# eagle-revg.net
KiCad netlist of a schematic drawn in EAGLE
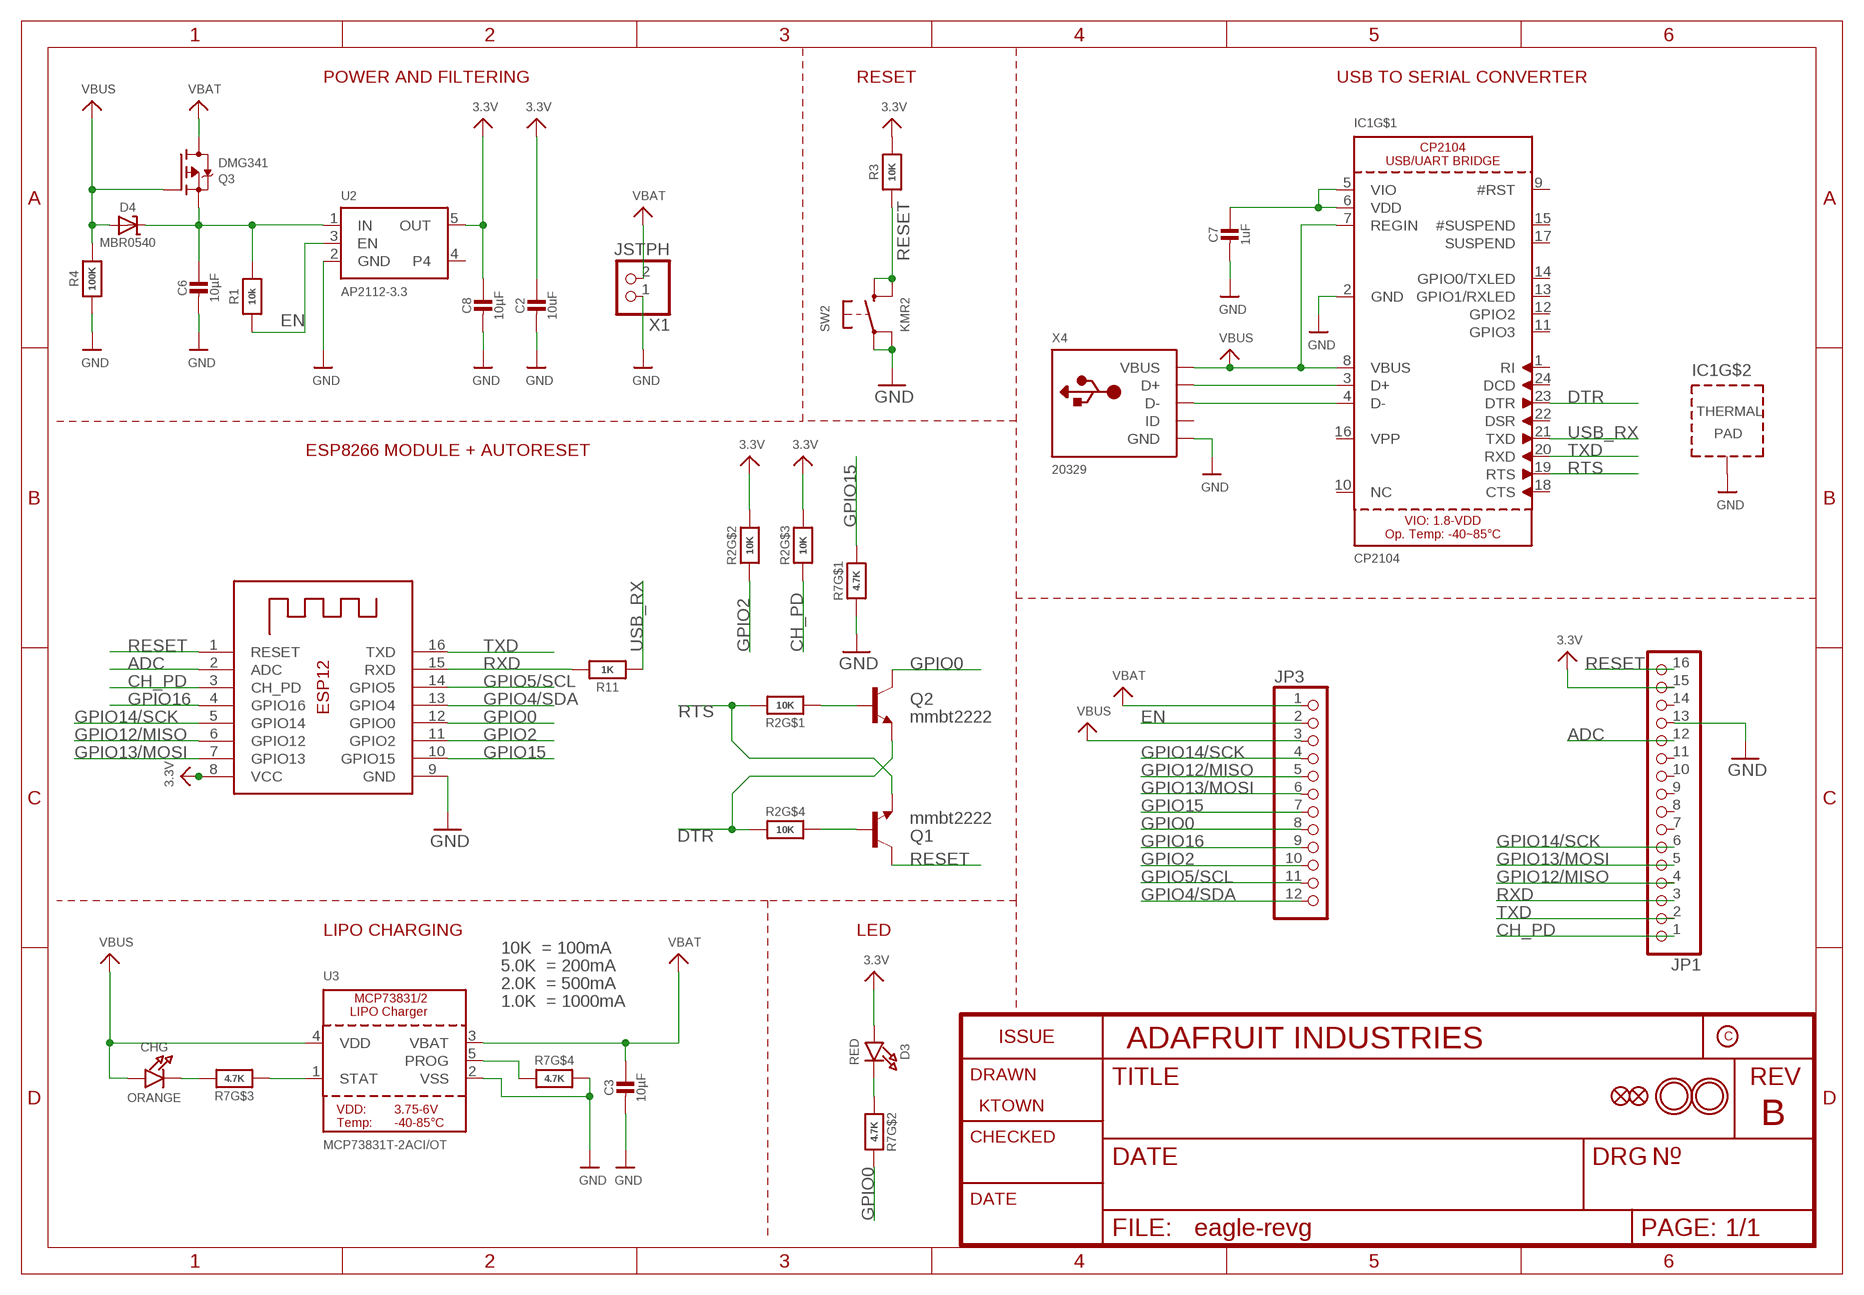
[diagram p0: schematic, sheet 1]

(export (version "E")
  (design (tool "Eeschema 10.0.6"))
  (components
    (comp (ref "C2")
      (value "10uF")
      (footprint "eagle-import:0805_10MGAP")
      (libsource (lib "eagle-import") (part "CAP_CERAMIC0805_10MGAP"))
    )
    (comp (ref "C3")
      (value "10µF")
      (footprint "eagle-import:0805-NO")
      (libsource (lib "eagle-import") (part "CAP_CERAMIC0805-NOOUTLINE"))
    )
    (comp (ref "C6")
      (value "10µF")
      (footprint "eagle-import:0805-NO")
      (libsource (lib "eagle-import") (part "CAP_CERAMIC0805-NOOUTLINE"))
    )
    (comp (ref "C7")
      (value "1uF")
      (footprint "eagle-import:0603-NO")
      (libsource (lib "eagle-import") (part "CAP_CERAMIC0603_NO"))
    )
    (comp (ref "C8")
      (value "10µF")
      (footprint "eagle-import:0805-NO")
      (fields (field (name "REV") "G"))
      (libsource (lib "eagle-import") (part "CAP_CERAMIC0805-NOOUTLINE"))
    )
    (comp (ref "CHG")
      (value "ORANGE")
      (footprint "eagle-import:CHIPLED_0603_NOOUTLINE")
      (libsource (lib "eagle-import") (part "LED0603_NOOUTLINE"))
    )
    (comp (ref "D3")
      (value "RED")
      (footprint "eagle-import:CHIPLED_0603_NOOUTLINE")
      (libsource (lib "eagle-import") (part "LED0603_NOOUTLINE"))
    )
    (comp (ref "D4")
      (value "MBR0540")
      (footprint "eagle-import:SOD-123")
      (libsource (lib "eagle-import") (part "DIODE-SCHOTTKYSOD-123"))
    )
    (comp (ref "IC1")
      (value "CP2104")
      (footprint "eagle-import:QFN24_4MM_SMSC")
      (libsource (lib "eagle-import") (part "CP2104"))
    )
    (comp (ref "JP1")
      (value "HEADER-1X16ROUND")
      (footprint "eagle-import:1X16_ROUND")
      (libsource (lib "eagle-import") (part "HEADER-1X16ROUND"))
    )
    (comp (ref "JP3")
      (value "HEADER-1X12")
      (footprint "eagle-import:1X12_ROUND")
      (libsource (lib "eagle-import") (part "HEADER-1X12"))
    )
    (comp (ref "Q1")
      (value "mmbt2222")
      (footprint "eagle-import:SOT23-3")
      (libsource (lib "eagle-import") (part "TRANSISTOR_NPNSOT23-3"))
    )
    (comp (ref "Q2")
      (value "mmbt2222")
      (footprint "eagle-import:SOT23-3")
      (libsource (lib "eagle-import") (part "TRANSISTOR_NPNSOT23-3"))
    )
    (comp (ref "Q3")
      (value "DMG341")
      (footprint "eagle-import:SOT23-R")
      (libsource (lib "eagle-import") (part "MOSFET-P"))
    )
    (comp (ref "R1")
      (value "10k")
      (footprint "eagle-import:0603-NO")
      (libsource (lib "eagle-import") (part "RESISTOR_0603_NOOUT"))
    )
    (comp (ref "R2")
      (value "10K")
      (footprint "eagle-import:RESPACK_4X0603_NO")
      (libsource (lib "eagle-import") (part "RESISTOR_4PACK_NO"))
    )
    (comp (ref "R3")
      (value "10K")
      (footprint "eagle-import:0603-NO")
      (libsource (lib "eagle-import") (part "RESISTOR_0603_NOOUT"))
    )
    (comp (ref "R4")
      (value "100K")
      (footprint "eagle-import:0603-NO")
      (libsource (lib "eagle-import") (part "RESISTOR_0603_NOOUT"))
    )
    (comp (ref "R7")
      (value "4.7K")
      (footprint "eagle-import:RESPACK_4X0603_NO")
      (libsource (lib "eagle-import") (part "RESISTOR_4PACK_NO"))
    )
    (comp (ref "R11")
      (value "1K")
      (footprint "eagle-import:0603-NO")
      (libsource (lib "eagle-import") (part "RESISTOR_0603_NOOUT"))
    )
    (comp (ref "SW2")
      (value "KMR2")
      (footprint "eagle-import:BTN_KMR2_4.6X2.8")
      (libsource (lib "eagle-import") (part "SWITCH_TACT_SMT4.6X2.8"))
    )
    (comp (ref "U$31")
      (value "MOUNTINGHOLE2.5")
      (footprint "eagle-import:MOUNTINGHOLE_2.5_PLATED")
      (libsource (lib "eagle-import") (part "MOUNTINGHOLE2.5"))
    )
    (comp (ref "U$32")
      (value "MOUNTINGHOLE2.5")
      (footprint "eagle-import:MOUNTINGHOLE_2.5_PLATED")
      (libsource (lib "eagle-import") (part "MOUNTINGHOLE2.5"))
    )
    (comp (ref "U$34")
      (value "FIDUCIAL_1MM")
      (footprint "eagle-import:FIDUCIAL_1MM")
      (libsource (lib "eagle-import") (part "FIDUCIAL_1MM"))
    )
    (comp (ref "U$35")
      (value "FIDUCIAL_1MM")
      (footprint "eagle-import:FIDUCIAL_1MM")
      (libsource (lib "eagle-import") (part "FIDUCIAL_1MM"))
    )
    (comp (ref "U2")
      (value "AP2112-3.3")
      (footprint "eagle-import:SOT23-5")
      (libsource (lib "eagle-import") (part "VREG_SOT23-5"))
    )
    (comp (ref "U3")
      (value "MCP73831T-2ACI/OT")
      (footprint "eagle-import:SOT23-5")
      (libsource (lib "eagle-import") (part "MCP73831/2"))
    )
    (comp (ref "X1")
      (value "JSTPH")
      (footprint "eagle-import:JSTPH2_BATT")
      (libsource (lib "eagle-import") (part "CON_JST_PH_2PIN_BATT"))
    )
    (comp (ref "X3")
      (value "ESP-12F")
      (footprint "eagle-import:ESP-12F")
      (libsource (lib "eagle-import") (part "ESP-12_DOIT_ESP8266"))
    )
    (comp (ref "X4")
      (value "20329")
      (footprint "eagle-import:4UCONN_20329_V2")
      (libsource (lib "eagle-import") (part "USB_MICRO_20329_V2"))
    )
  )
  (nets
    (net (code "1") (name "/ADC") (class "Default")
      (node (ref "JP1") (pin "12") (pinfunction "12_12") (pintype "passive"))
      (node (ref "X3") (pin "2") (pinfunction "ADC_2") (pintype "passive"))
    )
    (net (code "2") (name "/CH_PD") (class "Default")
      (node (ref "JP1") (pin "1") (pinfunction "1_1") (pintype "passive"))
      (node (ref "R2") (pin "3") (pinfunction "1_3") (pintype "passive"))
      (node (ref "X3") (pin "3") (pinfunction "CH_PD_3") (pintype "input"))
    )
    (net (code "3") (name "/DTR") (class "Default")
      (node (ref "IC1") (pin "23") (pinfunction "DTR_23") (pintype "output"))
      (node (ref "Q2") (pin "2") (pinfunction "E_2") (pintype "passive"))
      (node (ref "R2") (pin "4") (pinfunction "1_4") (pintype "passive"))
    )
    (net (code "4") (name "/EN") (class "Default")
      (node (ref "JP3") (pin "2") (pinfunction "2_2") (pintype "passive"))
      (node (ref "R1") (pin "1") (pinfunction "1_1") (pintype "passive"))
      (node (ref "U2") (pin "3") (pinfunction "EN_3") (pintype "input"))
    )
    (net (code "5") (name "/GPIO0") (class "Default")
      (node (ref "JP3") (pin "8") (pinfunction "8_8") (pintype "passive"))
      (node (ref "Q2") (pin "3") (pinfunction "C_3") (pintype "passive"))
      (node (ref "R7") (pin "7") (pinfunction "2_7") (pintype "passive"))
      (node (ref "X3") (pin "12") (pinfunction "GPIO0_12") (pintype "bidirectional"))
    )
    (net (code "6") (name "/GPIO2") (class "Default")
      (node (ref "JP3") (pin "10") (pinfunction "10_10") (pintype "passive"))
      (node (ref "R2") (pin "2") (pinfunction "1_2") (pintype "passive"))
      (node (ref "X3") (pin "11") (pinfunction "GPIO2_11") (pintype "bidirectional"))
    )
    (net (code "7") (name "/GPIO4{slash}SDA") (class "Default")
      (node (ref "JP3") (pin "12") (pinfunction "12_12") (pintype "passive"))
      (node (ref "X3") (pin "13") (pinfunction "GPIO4_13") (pintype "bidirectional"))
    )
    (net (code "8") (name "/GPIO5{slash}SCL") (class "Default")
      (node (ref "JP3") (pin "11") (pinfunction "11_11") (pintype "passive"))
      (node (ref "X3") (pin "14") (pinfunction "GPIO5_14") (pintype "bidirectional"))
    )
    (net (code "9") (name "/GPIO12{slash}MISO") (class "Default")
      (node (ref "JP1") (pin "4") (pinfunction "4_4") (pintype "passive"))
      (node (ref "JP3") (pin "5") (pinfunction "5_5") (pintype "passive"))
      (node (ref "X3") (pin "6") (pinfunction "GPIO12_6") (pintype "bidirectional"))
    )
    (net (code "10") (name "/GPIO13{slash}MOSI") (class "Default")
      (node (ref "JP1") (pin "5") (pinfunction "5_5") (pintype "passive"))
      (node (ref "JP3") (pin "6") (pinfunction "6_6") (pintype "passive"))
      (node (ref "X3") (pin "7") (pinfunction "GPIO13_7") (pintype "bidirectional"))
    )
    (net (code "11") (name "/GPIO14{slash}SCK") (class "Default")
      (node (ref "JP1") (pin "6") (pinfunction "6_6") (pintype "passive"))
      (node (ref "JP3") (pin "4") (pinfunction "4_4") (pintype "passive"))
      (node (ref "X3") (pin "5") (pinfunction "GPIO14_5") (pintype "bidirectional"))
    )
    (net (code "12") (name "/GPIO15") (class "Default")
      (node (ref "JP3") (pin "7") (pinfunction "7_7") (pintype "passive"))
      (node (ref "R7") (pin "8") (pinfunction "2_8") (pintype "passive"))
      (node (ref "X3") (pin "10") (pinfunction "GPIO15_10") (pintype "bidirectional"))
    )
    (net (code "13") (name "/GPIO16") (class "Default")
      (node (ref "JP3") (pin "9") (pinfunction "9_9") (pintype "passive"))
      (node (ref "X3") (pin "4") (pinfunction "GPIO16_4") (pintype "bidirectional"))
    )
    (net (code "14") (name "/RESET") (class "Default")
      (node (ref "JP1") (pin "16") (pinfunction "16_16") (pintype "passive"))
      (node (ref "Q1") (pin "3") (pinfunction "C_3") (pintype "passive"))
      (node (ref "R3") (pin "1") (pinfunction "1_1") (pintype "passive"))
      (node (ref "SW2") (pin "B") (pinfunction "S_B") (pintype "passive"))
      (node (ref "SW2") (pin "B'") (pinfunction "S1_B'") (pintype "passive"))
      (node (ref "X3") (pin "1") (pinfunction "RESET_1") (pintype "input"))
    )
    (net (code "15") (name "/RTS") (class "Default")
      (node (ref "IC1") (pin "19") (pinfunction "RTS_19") (pintype "output"))
      (node (ref "Q1") (pin "2") (pinfunction "E_2") (pintype "passive"))
      (node (ref "R2") (pin "8") (pinfunction "2_8") (pintype "passive"))
    )
    (net (code "16") (name "/RXD") (class "Default")
      (node (ref "JP1") (pin "3") (pinfunction "3_3") (pintype "passive"))
      (node (ref "R11") (pin "2") (pinfunction "2_2") (pintype "passive"))
      (node (ref "X3") (pin "15") (pinfunction "RXD_15") (pintype "input"))
    )
    (net (code "17") (name "/TXD") (class "Default")
      (node (ref "IC1") (pin "20") (pinfunction "RXD_20") (pintype "input"))
      (node (ref "JP1") (pin "2") (pinfunction "2_2") (pintype "passive"))
      (node (ref "X3") (pin "16") (pinfunction "TXD_16") (pintype "output"))
    )
    (net (code "18") (name "/USB_RX") (class "Default")
      (node (ref "IC1") (pin "21") (pinfunction "TXD_21") (pintype "output"))
      (node (ref "R11") (pin "1") (pinfunction "1_1") (pintype "passive"))
    )
    (net (code "19") (name "3.3V") (class "Default")
      (node (ref "C2") (pin "1") (pinfunction "1_1") (pintype "passive"))
      (node (ref "C8") (pin "1") (pinfunction "1_1") (pintype "passive"))
      (node (ref "D3") (pin "A") (pinfunction "A_A") (pintype "passive"))
      (node (ref "JP1") (pin "15") (pinfunction "15_15") (pintype "passive"))
      (node (ref "R2") (pin "6") (pinfunction "2_6") (pintype "passive"))
      (node (ref "R2") (pin "7") (pinfunction "2_7") (pintype "passive"))
      (node (ref "R3") (pin "2") (pinfunction "2_2") (pintype "passive"))
      (node (ref "U2") (pin "5") (pinfunction "OUT_5") (pintype "power_in"))
      (node (ref "X3") (pin "8") (pinfunction "VCC_8") (pintype "power_in"))
    )
    (net (code "20") (name "GND") (class "Default")
      (node (ref "C2") (pin "2") (pinfunction "2_2") (pintype "passive"))
      (node (ref "C3") (pin "2") (pinfunction "2_2") (pintype "passive"))
      (node (ref "C6") (pin "2") (pinfunction "2_2") (pintype "passive"))
      (node (ref "C7") (pin "2") (pinfunction "2_2") (pintype "passive"))
      (node (ref "C8") (pin "2") (pinfunction "2_2") (pintype "passive"))
      (node (ref "IC1") (pin "2") (pinfunction "GND_2") (pintype "power_in"))
      (node (ref "IC1") (pin "THERM") (pinfunction "TP_THERM") (pintype "power_in"))
      (node (ref "JP1") (pin "13") (pinfunction "13_13") (pintype "passive"))
      (node (ref "R4") (pin "1") (pinfunction "1_1") (pintype "passive"))
      (node (ref "R7") (pin "1") (pinfunction "1_1") (pintype "passive"))
      (node (ref "R7") (pin "5") (pinfunction "2_5") (pintype "passive"))
      (node (ref "SW2") (pin "A") (pinfunction "P_A") (pintype "passive"))
      (node (ref "SW2") (pin "A'") (pinfunction "P1_A'") (pintype "passive"))
      (node (ref "U2") (pin "2") (pinfunction "GND_2") (pintype "power_in"))
      (node (ref "U3") (pin "2") (pinfunction "VSS_2") (pintype "power_in"))
      (node (ref "X1") (pin "1") (pinfunction "1_1") (pintype "passive"))
      (node (ref "X3") (pin "9") (pinfunction "GND_9") (pintype "power_in"))
      (node (ref "X4") (pin "BASE@1") (pinfunction "GND_BASE@1") (pintype "power_in"))
      (node (ref "X4") (pin "BASE@2") (pinfunction "GND_BASE@2") (pintype "power_in"))
      (node (ref "X4") (pin "GND") (pinfunction "GND_GND") (pintype "power_in"))
      (node (ref "X4") (pin "SPRT@1") (pinfunction "GND_SPRT@1") (pintype "power_in"))
      (node (ref "X4") (pin "SPRT@2") (pinfunction "GND_SPRT@2") (pintype "power_in"))
      (node (ref "X4") (pin "SPRT@3") (pinfunction "GND_SPRT@3") (pintype "power_in"))
      (node (ref "X4") (pin "SPRT@4") (pinfunction "GND_SPRT@4") (pintype "power_in"))
    )
    (net (code "21") (name "Net-(IC1A-D+)") (class "Default")
      (node (ref "IC1") (pin "3") (pinfunction "D+_3") (pintype "bidirectional"))
      (node (ref "X4") (pin "D+") (pinfunction "D+_D+") (pintype "bidirectional"))
    )
    (net (code "22") (name "Net-(IC1A-D-)") (class "Default")
      (node (ref "IC1") (pin "4") (pinfunction "D-_4") (pintype "bidirectional"))
      (node (ref "X4") (pin "D-") (pinfunction "D-_D-") (pintype "bidirectional"))
    )
    (net (code "23") (name "Net-(IC1A-VDD)") (class "Default")
      (node (ref "C7") (pin "1") (pinfunction "1_1") (pintype "passive"))
      (node (ref "IC1") (pin "5") (pinfunction "VIO_5") (pintype "power_in"))
      (node (ref "IC1") (pin "6") (pinfunction "VDD_6") (pintype "power_in"))
    )
    (net (code "24") (name "Net-(Q1-B)") (class "Default")
      (node (ref "Q1") (pin "1") (pinfunction "B_1") (pintype "passive"))
      (node (ref "R2") (pin "5") (pinfunction "2_5") (pintype "passive"))
    )
    (net (code "25") (name "Net-(Q2-B)") (class "Default")
      (node (ref "Q2") (pin "1") (pinfunction "B_1") (pintype "passive"))
      (node (ref "R2") (pin "1") (pinfunction "1_1") (pintype "passive"))
    )
    (net (code "26") (name "Net-(Q3-S)") (class "Default")
      (node (ref "C6") (pin "1") (pinfunction "1_1") (pintype "passive"))
      (node (ref "D4") (pin "C") (pinfunction "C_C") (pintype "passive"))
      (node (ref "Q3") (pin "2") (pinfunction "S_2") (pintype "passive"))
      (node (ref "R1") (pin "2") (pinfunction "2_2") (pintype "passive"))
      (node (ref "U2") (pin "1") (pinfunction "IN_1") (pintype "power_in"))
    )
    (net (code "27") (name "Net-(R7B-1)") (class "Default")
      (node (ref "D3") (pin "C") (pinfunction "C_C") (pintype "passive"))
      (node (ref "R7") (pin "2") (pinfunction "1_2") (pintype "passive"))
    )
    (net (code "28") (name "Net-(R7C-1)") (class "Default")
      (node (ref "R7") (pin "3") (pinfunction "1_3") (pintype "passive"))
      (node (ref "U3") (pin "1") (pinfunction "STAT_1") (pintype "output"))
    )
    (net (code "29") (name "Net-(R7C-2)") (class "Default")
      (node (ref "CHG") (pin "C") (pinfunction "C_C") (pintype "passive"))
      (node (ref "R7") (pin "6") (pinfunction "2_6") (pintype "passive"))
    )
    (net (code "30") (name "Net-(R7D-1)") (class "Default")
      (node (ref "R7") (pin "4") (pinfunction "1_4") (pintype "passive"))
      (node (ref "U3") (pin "5") (pinfunction "PROG_5") (pintype "input"))
    )
    (net (code "31") (name "VBAT") (class "Default")
      (node (ref "C3") (pin "1") (pinfunction "1_1") (pintype "passive"))
      (node (ref "JP3") (pin "1") (pinfunction "1_1") (pintype "passive"))
      (node (ref "Q3") (pin "3") (pinfunction "D_3") (pintype "passive"))
      (node (ref "U3") (pin "3") (pinfunction "VBAT_3") (pintype "power_in"))
      (node (ref "X1") (pin "2") (pinfunction "2_2") (pintype "passive"))
    )
    (net (code "32") (name "VBUS") (class "Default")
      (node (ref "CHG") (pin "A") (pinfunction "A_A") (pintype "passive"))
      (node (ref "D4") (pin "A") (pinfunction "A_A") (pintype "passive"))
      (node (ref "IC1") (pin "7") (pinfunction "REGIN_7") (pintype "power_in"))
      (node (ref "IC1") (pin "8") (pinfunction "VBUS_8") (pintype "power_in"))
      (node (ref "JP3") (pin "3") (pinfunction "3_3") (pintype "passive"))
      (node (ref "Q3") (pin "1") (pinfunction "G_1") (pintype "passive"))
      (node (ref "R4") (pin "2") (pinfunction "2_2") (pintype "passive"))
      (node (ref "U3") (pin "4") (pinfunction "VDD_4") (pintype "power_in"))
      (node (ref "X4") (pin "VBUS") (pinfunction "VBUS_VBUS") (pintype "power_in"))
    )
    (net (code "33") (name "unconnected-(IC1A-#RST-Pad9)") (class "Default")
      (node (ref "IC1") (pin "9") (pinfunction "#RST_9") (pintype "bidirectional"))
    )
    (net (code "34") (name "unconnected-(IC1A-#SUSPEND-Pad15)") (class "Default")
      (node (ref "IC1") (pin "15") (pinfunction "#SUSPEND_15") (pintype "output"))
    )
    (net (code "35") (name "unconnected-(IC1A-CTS-Pad18)") (class "Default")
      (node (ref "IC1") (pin "18") (pinfunction "CTS_18") (pintype "input"))
    )
    (net (code "36") (name "unconnected-(IC1A-DCD-Pad24)") (class "Default")
      (node (ref "IC1") (pin "24") (pinfunction "DCD_24") (pintype "input"))
    )
    (net (code "37") (name "unconnected-(IC1A-DSR-Pad22)") (class "Default")
      (node (ref "IC1") (pin "22") (pinfunction "DSR_22") (pintype "input"))
    )
    (net (code "38") (name "unconnected-(IC1A-GPIO0{slash}TXLED-Pad14)") (class "Default")
      (node (ref "IC1") (pin "14") (pinfunction "GPIO0/TXLED_14") (pintype "bidirectional"))
    )
    (net (code "39") (name "unconnected-(IC1A-GPIO1{slash}RXLED-Pad13)") (class "Default")
      (node (ref "IC1") (pin "13") (pinfunction "GPIO1/RXLED_13") (pintype "bidirectional"))
    )
    (net (code "40") (name "unconnected-(IC1A-GPIO2-Pad12)") (class "Default")
      (node (ref "IC1") (pin "12") (pinfunction "GPIO2_12") (pintype "bidirectional"))
    )
    (net (code "41") (name "unconnected-(IC1A-GPIO3-Pad11)") (class "Default")
      (node (ref "IC1") (pin "11") (pinfunction "GPIO3_11") (pintype "bidirectional"))
    )
    (net (code "42") (name "unconnected-(IC1A-NC-Pad10)") (class "Default")
      (node (ref "IC1") (pin "10") (pinfunction "NC_10") (pintype "no_connect"))
    )
    (net (code "43") (name "unconnected-(IC1A-RI-Pad1)") (class "Default")
      (node (ref "IC1") (pin "1") (pinfunction "RI_1") (pintype "input"))
    )
    (net (code "44") (name "unconnected-(IC1A-SUSPEND-Pad17)") (class "Default")
      (node (ref "IC1") (pin "17") (pinfunction "SUSPEND_17") (pintype "output"))
    )
    (net (code "45") (name "unconnected-(IC1A-VPP-Pad16)") (class "Default")
      (node (ref "IC1") (pin "16") (pinfunction "VPP_16") (pintype "bidirectional"))
    )
    (net (code "46") (name "unconnected-(JP1-Pad7)") (class "Default")
      (node (ref "JP1") (pin "7") (pinfunction "7_7") (pintype "passive"))
    )
    (net (code "47") (name "unconnected-(JP1-Pad8)") (class "Default")
      (node (ref "JP1") (pin "8") (pinfunction "8_8") (pintype "passive"))
    )
    (net (code "48") (name "unconnected-(JP1-Pad9)") (class "Default")
      (node (ref "JP1") (pin "9") (pinfunction "9_9") (pintype "passive"))
    )
    (net (code "49") (name "unconnected-(JP1-Pad10)") (class "Default")
      (node (ref "JP1") (pin "10") (pinfunction "10_10") (pintype "passive"))
    )
    (net (code "50") (name "unconnected-(JP1-Pad11)") (class "Default")
      (node (ref "JP1") (pin "11") (pinfunction "11_11") (pintype "passive"))
    )
    (net (code "51") (name "unconnected-(JP1-Pad14)") (class "Default")
      (node (ref "JP1") (pin "14") (pinfunction "14_14") (pintype "passive"))
    )
    (net (code "52") (name "unconnected-(U2-P4-Pad4)") (class "Default")
      (node (ref "U2") (pin "4") (pinfunction "P4_4") (pintype "bidirectional"))
    )
    (net (code "53") (name "unconnected-(X4-PadID)") (class "Default")
      (node (ref "X4") (pin "ID") (pinfunction "ID_ID") (pintype "bidirectional"))
    )
  )
)
